# untitled.net
KiCad netlist of a schematic drawn in EAGLE
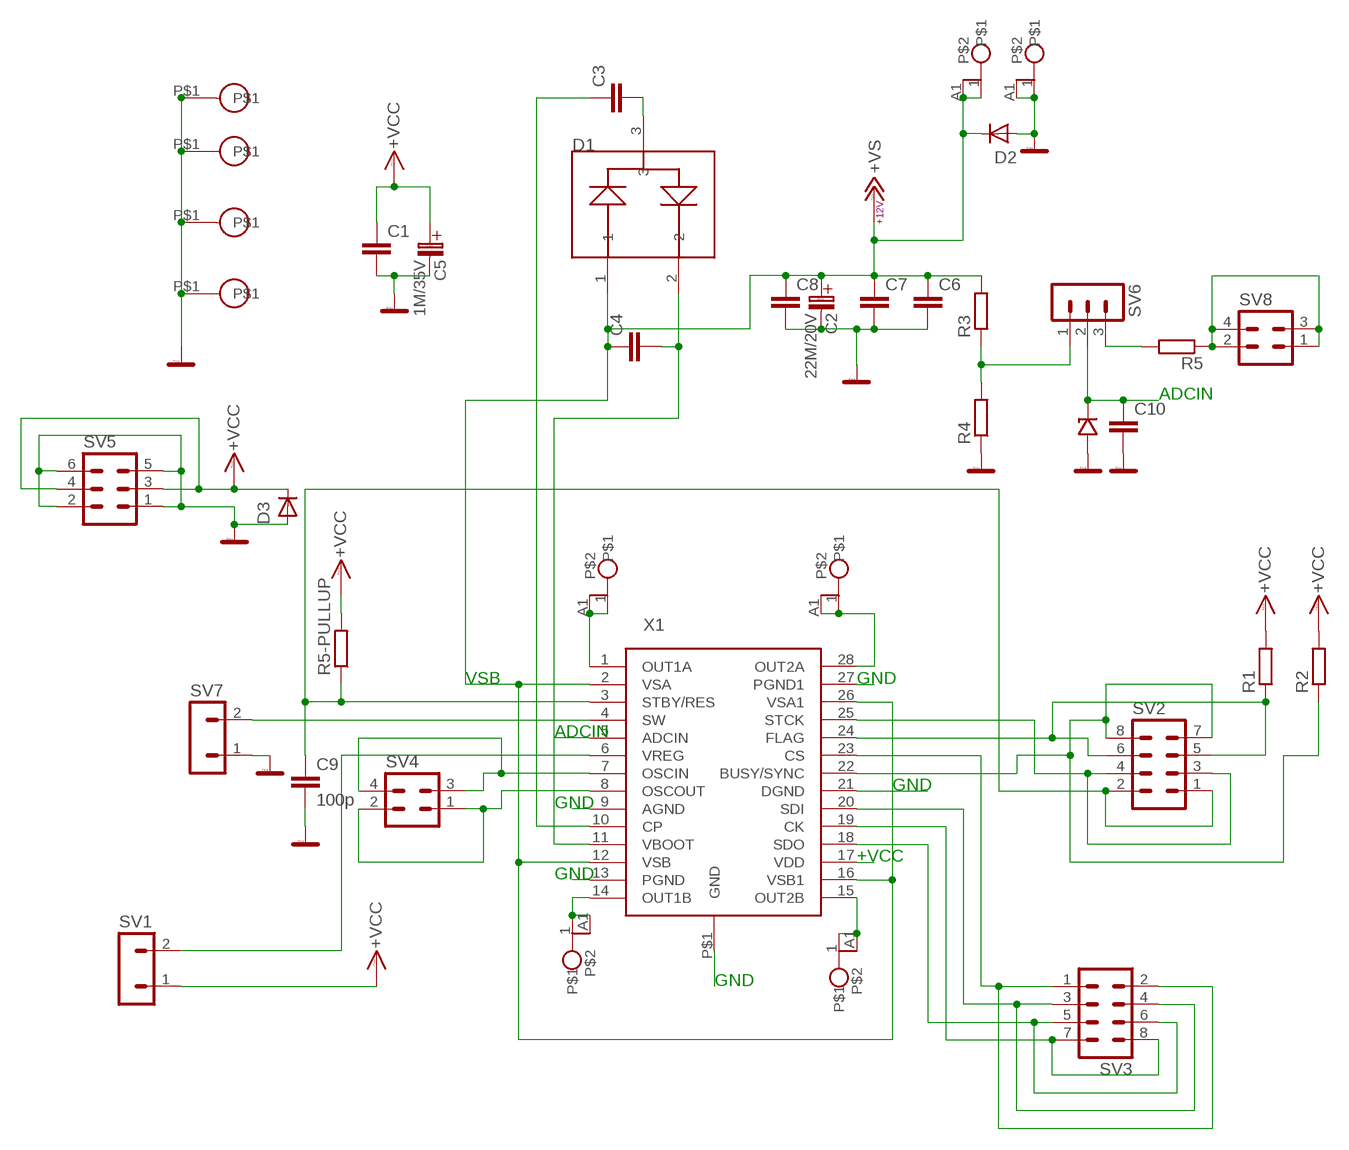
[diagram p0: schematic, sheet 1]

(export (version "E")
  (design (tool "Eeschema 10.0.6"))
  (components
    (comp (ref "C1")
      (value "C-EUC0805")
      (footprint "eagle-import:C0805")
      (libsource (lib "eagle-import") (part "C-EUC0805"))
    )
    (comp (ref "C2")
      (value "22M/20V")
      (footprint "eagle-import:D")
      (libsource (lib "eagle-import") (part "22M/20V"))
    )
    (comp (ref "C3")
      (value "C-EUC0805")
      (footprint "eagle-import:C0805")
      (libsource (lib "eagle-import") (part "C-EUC0805"))
    )
    (comp (ref "C4")
      (value "C-EUC0805")
      (footprint "eagle-import:C0805")
      (libsource (lib "eagle-import") (part "C-EUC0805"))
    )
    (comp (ref "C5")
      (value "1M/35V")
      (footprint "eagle-import:B")
      (libsource (lib "eagle-import") (part "1M/35V"))
    )
    (comp (ref "C6")
      (value "C-EUC0805")
      (footprint "eagle-import:C0805")
      (libsource (lib "eagle-import") (part "C-EUC0805"))
    )
    (comp (ref "C7")
      (value "C-EUC0805")
      (footprint "eagle-import:C0805")
      (libsource (lib "eagle-import") (part "C-EUC0805"))
    )
    (comp (ref "C8")
      (value "C-EUC0805")
      (footprint "eagle-import:C0805")
      (libsource (lib "eagle-import") (part "C-EUC0805"))
    )
    (comp (ref "C9")
      (value "100p")
      (footprint "eagle-import:C0805")
      (libsource (lib "eagle-import") (part "C-EUC0805"))
    )
    (comp (ref "C10")
      (value "C-EUC0805")
      (footprint "eagle-import:C0805")
      (libsource (lib "eagle-import") (part "C-EUC0805"))
    )
    (comp (ref "CON1")
      (value "WAGO256")
      (footprint "eagle-import:WAGO256")
      (libsource (lib "eagle-import") (part "WAGO256"))
    )
    (comp (ref "CON2")
      (value "WAGO256")
      (footprint "eagle-import:WAGO256")
      (libsource (lib "eagle-import") (part "WAGO256"))
    )
    (comp (ref "CON3")
      (value "WAGO256")
      (footprint "eagle-import:WAGO256")
      (libsource (lib "eagle-import") (part "WAGO256"))
    )
    (comp (ref "CON4")
      (value "WAGO256")
      (footprint "eagle-import:WAGO256")
      (libsource (lib "eagle-import") (part "WAGO256"))
    )
    (comp (ref "CON5")
      (value "WAGO256")
      (footprint "eagle-import:WAGO256")
      (libsource (lib "eagle-import") (part "WAGO256"))
    )
    (comp (ref "CON6")
      (value "WAGO256")
      (footprint "eagle-import:WAGO256")
      (libsource (lib "eagle-import") (part "WAGO256"))
    )
    (comp (ref "D1")
      (value "BAR43S")
      (footprint "eagle-import:SOT23")
      (libsource (lib "eagle-import") (part "BAR43S"))
    )
    (comp (ref "D2")
      (value "D-OB.")
      (footprint "eagle-import:SMB")
      (libsource (lib "eagle-import") (part "D-OB."))
    )
    (comp (ref "D3")
      (value "D-OB.SMA")
      (footprint "eagle-import:SMA")
      (libsource (lib "eagle-import") (part "D-OB.SMA"))
    )
    (comp (ref "D4")
      (value "D-ZENEROVA")
      (footprint "eagle-import:MINIMELF")
      (libsource (lib "eagle-import") (part "D-ZENEROVA"))
    )
    (comp (ref "R1")
      (value "R-EU_R0805")
      (footprint "eagle-import:R0805")
      (libsource (lib "eagle-import") (part "R-EU_R0805"))
    )
    (comp (ref "R2")
      (value "R-EU_R0805")
      (footprint "eagle-import:R0805")
      (libsource (lib "eagle-import") (part "R-EU_R0805"))
    )
    (comp (ref "R3")
      (value "R-EU_R0805")
      (footprint "eagle-import:R0805")
      (libsource (lib "eagle-import") (part "R-EU_R0805"))
    )
    (comp (ref "R4")
      (value "R-EU_R0805")
      (footprint "eagle-import:R0805")
      (libsource (lib "eagle-import") (part "R-EU_R0805"))
    )
    (comp (ref "R5")
      (value "R-EU_R0805")
      (footprint "eagle-import:R0805")
      (libsource (lib "eagle-import") (part "R-EU_R0805"))
    )
    (comp (ref "R5-PULLUP")
      (value "R-EU_R0805")
      (footprint "eagle-import:R0805")
      (libsource (lib "eagle-import") (part "R-EU_R0805"))
    )
    (comp (ref "SV1")
      (value "MA02-1")
      (footprint "eagle-import:MA02-1")
      (libsource (lib "eagle-import") (part "MA02-1"))
    )
    (comp (ref "SV2")
      (value "MA04-2")
      (footprint "eagle-import:MA04-2")
      (libsource (lib "eagle-import") (part "MA04-2"))
    )
    (comp (ref "SV3")
      (value "MA04-2")
      (footprint "eagle-import:MA04-2")
      (libsource (lib "eagle-import") (part "MA04-2"))
    )
    (comp (ref "SV4")
      (value "MA02-2")
      (footprint "eagle-import:MA02-2")
      (libsource (lib "eagle-import") (part "MA02-2"))
    )
    (comp (ref "SV5")
      (value "MA03-2")
      (footprint "eagle-import:MA03-2")
      (libsource (lib "eagle-import") (part "MA03-2"))
    )
    (comp (ref "SV6")
      (value "MA03-1")
      (footprint "eagle-import:MA03-1")
      (libsource (lib "eagle-import") (part "MA03-1"))
    )
    (comp (ref "SV7")
      (value "MA02-1")
      (footprint "eagle-import:MA02-1")
      (libsource (lib "eagle-import") (part "MA02-1"))
    )
    (comp (ref "SV8")
      (value "MA02-2")
      (footprint "eagle-import:MA02-2")
      (libsource (lib "eagle-import") (part "MA02-2"))
    )
    (comp (ref "X1")
      (value "L6470")
      (footprint "eagle-import:HTSSOP28")
      (libsource (lib "eagle-import") (part "L6470"))
    )
    (comp (ref "X3")
      (value "SROUB3M")
      (footprint "eagle-import:SROUB3M")
      (libsource (lib "eagle-import") (part "SROUB3M"))
    )
    (comp (ref "X4")
      (value "SROUB3M")
      (footprint "eagle-import:SROUB3M")
      (libsource (lib "eagle-import") (part "SROUB3M"))
    )
    (comp (ref "X5")
      (value "SROUB3M")
      (footprint "eagle-import:SROUB3M")
      (libsource (lib "eagle-import") (part "SROUB3M"))
    )
    (comp (ref "X6")
      (value "SROUB3M")
      (footprint "eagle-import:SROUB3M")
      (libsource (lib "eagle-import") (part "SROUB3M"))
    )
  )
  (nets
    (net (code "1") (name "+VCC") (class "Default")
      (node (ref "C1") (pin "1") (pinfunction "1_1") (pintype "passive"))
      (node (ref "C5") (pin "+") (pinfunction "C_EL+_+") (pintype "passive"))
      (node (ref "D3") (pin "K") (pinfunction "C_K") (pintype "passive"))
      (node (ref "R1") (pin "2") (pinfunction "2_2") (pintype "passive"))
      (node (ref "R2") (pin "2") (pinfunction "2_2") (pintype "passive"))
      (node (ref "R5-PULLUP") (pin "2") (pinfunction "2_2") (pintype "passive"))
      (node (ref "SV1") (pin "1") (pinfunction "1_1") (pintype "passive"))
      (node (ref "SV5") (pin "3") (pinfunction "3_3") (pintype "passive"))
      (node (ref "SV5") (pin "4") (pinfunction "4_4") (pintype "passive"))
      (node (ref "X1") (pin "17") (pinfunction "VDD_17") (pintype "bidirectional"))
    )
    (net (code "2") (name "+VS") (class "Default")
      (node (ref "C2") (pin "+") (pinfunction "C_EL+_+") (pintype "passive"))
      (node (ref "C4") (pin "1") (pinfunction "1_1") (pintype "passive"))
      (node (ref "C6") (pin "1") (pinfunction "1_1") (pintype "passive"))
      (node (ref "C7") (pin "1") (pinfunction "1_1") (pintype "passive"))
      (node (ref "C8") (pin "1") (pinfunction "1_1") (pintype "passive"))
      (node (ref "CON6") (pin "1") (pinfunction "P$1_1") (pintype "passive"))
      (node (ref "CON6") (pin "A1") (pinfunction "P$2_A1") (pintype "passive"))
      (node (ref "D1") (pin "1") (pinfunction "1_1") (pintype "bidirectional"))
      (node (ref "D2") (pin "K") (pinfunction "C_K") (pintype "passive"))
      (node (ref "R3") (pin "2") (pinfunction "2_2") (pintype "passive"))
      (node (ref "X1") (pin "12") (pinfunction "VSB_12") (pintype "bidirectional"))
      (node (ref "X1") (pin "16") (pinfunction "VSB1_16") (pintype "bidirectional"))
      (node (ref "X1") (pin "2") (pinfunction "VSA_2") (pintype "bidirectional"))
      (node (ref "X1") (pin "26") (pinfunction "VSA1_26") (pintype "bidirectional"))
    )
    (net (code "3") (name "/ADCIN") (class "Default")
      (node (ref "C10") (pin "1") (pinfunction "1_1") (pintype "passive"))
      (node (ref "D4") (pin "C") (pinfunction "K_C") (pintype "passive"))
      (node (ref "SV6") (pin "2") (pinfunction "2_2") (pintype "passive"))
      (node (ref "X1") (pin "5") (pinfunction "ADCIN_5") (pintype "bidirectional"))
    )
    (net (code "4") (name "GND") (class "Default")
      (node (ref "C1") (pin "2") (pinfunction "2_2") (pintype "passive"))
      (node (ref "C10") (pin "2") (pinfunction "2_2") (pintype "passive"))
      (node (ref "C2") (pin "-") (pinfunction "C_EL-_-") (pintype "passive"))
      (node (ref "C5") (pin "-") (pinfunction "C_EL-_-") (pintype "passive"))
      (node (ref "C6") (pin "2") (pinfunction "2_2") (pintype "passive"))
      (node (ref "C7") (pin "2") (pinfunction "2_2") (pintype "passive"))
      (node (ref "C8") (pin "2") (pinfunction "2_2") (pintype "passive"))
      (node (ref "C9") (pin "2") (pinfunction "2_2") (pintype "passive"))
      (node (ref "CON5") (pin "1") (pinfunction "P$1_1") (pintype "passive"))
      (node (ref "CON5") (pin "A1") (pinfunction "P$2_A1") (pintype "passive"))
      (node (ref "D2") (pin "A") (pinfunction "A_A") (pintype "passive"))
      (node (ref "D3") (pin "A") (pinfunction "A_A") (pintype "passive"))
      (node (ref "D4") (pin "A") (pinfunction "A_A") (pintype "passive"))
      (node (ref "R4") (pin "1") (pinfunction "1_1") (pintype "passive"))
      (node (ref "SV5") (pin "1") (pinfunction "1_1") (pintype "passive"))
      (node (ref "SV5") (pin "2") (pinfunction "2_2") (pintype "passive"))
      (node (ref "SV5") (pin "5") (pinfunction "5_5") (pintype "passive"))
      (node (ref "SV5") (pin "6") (pinfunction "6_6") (pintype "passive"))
      (node (ref "SV7") (pin "1") (pinfunction "1_1") (pintype "passive"))
      (node (ref "X1") (pin "13") (pinfunction "PGND_13") (pintype "bidirectional"))
      (node (ref "X1") (pin "21") (pinfunction "DGND_21") (pintype "bidirectional"))
      (node (ref "X1") (pin "27") (pinfunction "PGND1_27") (pintype "bidirectional"))
      (node (ref "X1") (pin "9") (pinfunction "AGND_9") (pintype "bidirectional"))
      (node (ref "X1") (pin "P$1") (pinfunction "GND_P$1") (pintype "bidirectional"))
      (node (ref "X3") (pin "P$1") (pinfunction "P$1_P$1") (pintype "output"))
      (node (ref "X4") (pin "P$1") (pinfunction "P$1_P$1") (pintype "output"))
      (node (ref "X5") (pin "P$1") (pinfunction "P$1_P$1") (pintype "output"))
      (node (ref "X6") (pin "P$1") (pinfunction "P$1_P$1") (pintype "output"))
    )
    (net (code "5") (name "Net-(C3-Pad2)") (class "Default")
      (node (ref "C3") (pin "2") (pinfunction "2_2") (pintype "passive"))
      (node (ref "D1") (pin "3") (pinfunction "3_3") (pintype "bidirectional"))
    )
    (net (code "6") (name "Net-(CON1-P$1)") (class "Default")
      (node (ref "CON1") (pin "1") (pinfunction "P$1_1") (pintype "passive"))
      (node (ref "CON1") (pin "A1") (pinfunction "P$2_A1") (pintype "passive"))
      (node (ref "X1") (pin "14") (pinfunction "OUT1B_14") (pintype "bidirectional"))
    )
    (net (code "7") (name "Net-(CON2-P$1)") (class "Default")
      (node (ref "CON2") (pin "1") (pinfunction "P$1_1") (pintype "passive"))
      (node (ref "CON2") (pin "A1") (pinfunction "P$2_A1") (pintype "passive"))
      (node (ref "X1") (pin "15") (pinfunction "OUT2B_15") (pintype "bidirectional"))
    )
    (net (code "8") (name "Net-(CON3-P$1)") (class "Default")
      (node (ref "CON3") (pin "1") (pinfunction "P$1_1") (pintype "passive"))
      (node (ref "CON3") (pin "A1") (pinfunction "P$2_A1") (pintype "passive"))
      (node (ref "X1") (pin "1") (pinfunction "OUT1A_1") (pintype "bidirectional"))
    )
    (net (code "9") (name "Net-(CON4-P$1)") (class "Default")
      (node (ref "CON4") (pin "1") (pinfunction "P$1_1") (pintype "passive"))
      (node (ref "CON4") (pin "A1") (pinfunction "P$2_A1") (pintype "passive"))
      (node (ref "X1") (pin "28") (pinfunction "OUT2A_28") (pintype "bidirectional"))
    )
    (net (code "10") (name "Net-(R3-Pad1)") (class "Default")
      (node (ref "R3") (pin "1") (pinfunction "1_1") (pintype "passive"))
      (node (ref "R4") (pin "2") (pinfunction "2_2") (pintype "passive"))
      (node (ref "SV6") (pin "1") (pinfunction "1_1") (pintype "passive"))
    )
    (net (code "11") (name "Net-(R5-Pad1)") (class "Default")
      (node (ref "R5") (pin "1") (pinfunction "1_1") (pintype "passive"))
      (node (ref "SV8") (pin "1") (pinfunction "1_1") (pintype "passive"))
      (node (ref "SV8") (pin "2") (pinfunction "2_2") (pintype "passive"))
      (node (ref "SV8") (pin "3") (pinfunction "3_3") (pintype "passive"))
      (node (ref "SV8") (pin "4") (pinfunction "4_4") (pintype "passive"))
    )
    (net (code "12") (name "Net-(R5-Pad2)") (class "Default")
      (node (ref "R5") (pin "2") (pinfunction "2_2") (pintype "passive"))
      (node (ref "SV6") (pin "3") (pinfunction "3_3") (pintype "passive"))
    )
    (net (code "13") (name "Net-(SV1-3)") (class "Default")
      (node (ref "SV1") (pin "2") (pinfunction "3_2") (pintype "passive"))
      (node (ref "X1") (pin "6") (pinfunction "VREG_6") (pintype "bidirectional"))
    )
    (net (code "14") (name "Net-(SV7-3)") (class "Default")
      (node (ref "SV7") (pin "2") (pinfunction "3_2") (pintype "passive"))
      (node (ref "X1") (pin "4") (pinfunction "SW_4") (pintype "bidirectional"))
    )
    (net (code "15") (name "Net-(X1-BUSY{slash}SYNC)") (class "Default")
      (node (ref "R2") (pin "1") (pinfunction "1_1") (pintype "passive"))
      (node (ref "SV2") (pin "7") (pinfunction "7_7") (pintype "passive"))
      (node (ref "SV2") (pin "8") (pinfunction "8_8") (pintype "passive"))
      (node (ref "X1") (pin "22") (pinfunction "BUSY/SYNC_22") (pintype "bidirectional"))
    )
    (net (code "16") (name "Net-(X1-CK)") (class "Default")
      (node (ref "SV3") (pin "7") (pinfunction "7_7") (pintype "passive"))
      (node (ref "SV3") (pin "8") (pinfunction "8_8") (pintype "passive"))
      (node (ref "X1") (pin "19") (pinfunction "CK_19") (pintype "bidirectional"))
    )
    (net (code "17") (name "Net-(X1-CP)") (class "Default")
      (node (ref "C3") (pin "1") (pinfunction "1_1") (pintype "passive"))
      (node (ref "X1") (pin "10") (pinfunction "CP_10") (pintype "bidirectional"))
    )
    (net (code "18") (name "Net-(X1-CS)") (class "Default")
      (node (ref "SV3") (pin "1") (pinfunction "1_1") (pintype "passive"))
      (node (ref "SV3") (pin "2") (pinfunction "2_2") (pintype "passive"))
      (node (ref "X1") (pin "23") (pinfunction "CS_23") (pintype "bidirectional"))
    )
    (net (code "19") (name "Net-(X1-FLAG)") (class "Default")
      (node (ref "R1") (pin "1") (pinfunction "1_1") (pintype "passive"))
      (node (ref "SV2") (pin "5") (pinfunction "5_5") (pintype "passive"))
      (node (ref "SV2") (pin "6") (pinfunction "6_6") (pintype "passive"))
      (node (ref "X1") (pin "24") (pinfunction "FLAG_24") (pintype "bidirectional"))
    )
    (net (code "20") (name "Net-(X1-OSCIN)") (class "Default")
      (node (ref "SV4") (pin "3") (pinfunction "3_3") (pintype "passive"))
      (node (ref "SV4") (pin "4") (pinfunction "4_4") (pintype "passive"))
      (node (ref "X1") (pin "7") (pinfunction "OSCIN_7") (pintype "bidirectional"))
    )
    (net (code "21") (name "Net-(X1-OSCOUT)") (class "Default")
      (node (ref "SV4") (pin "1") (pinfunction "1_1") (pintype "passive"))
      (node (ref "SV4") (pin "2") (pinfunction "2_2") (pintype "passive"))
      (node (ref "X1") (pin "8") (pinfunction "OSCOUT_8") (pintype "bidirectional"))
    )
    (net (code "22") (name "Net-(X1-SDI)") (class "Default")
      (node (ref "SV3") (pin "3") (pinfunction "3_3") (pintype "passive"))
      (node (ref "SV3") (pin "4") (pinfunction "4_4") (pintype "passive"))
      (node (ref "X1") (pin "20") (pinfunction "SDI_20") (pintype "bidirectional"))
    )
    (net (code "23") (name "Net-(X1-SDO)") (class "Default")
      (node (ref "SV3") (pin "5") (pinfunction "5_5") (pintype "passive"))
      (node (ref "SV3") (pin "6") (pinfunction "6_6") (pintype "passive"))
      (node (ref "X1") (pin "18") (pinfunction "SDO_18") (pintype "bidirectional"))
    )
    (net (code "24") (name "Net-(X1-STBY{slash}RES)") (class "Default")
      (node (ref "C9") (pin "1") (pinfunction "1_1") (pintype "passive"))
      (node (ref "R5-PULLUP") (pin "1") (pinfunction "1_1") (pintype "passive"))
      (node (ref "SV2") (pin "1") (pinfunction "1_1") (pintype "passive"))
      (node (ref "SV2") (pin "2") (pinfunction "2_2") (pintype "passive"))
      (node (ref "X1") (pin "3") (pinfunction "STBY/RES_3") (pintype "bidirectional"))
    )
    (net (code "25") (name "Net-(X1-STCK)") (class "Default")
      (node (ref "SV2") (pin "3") (pinfunction "3_3") (pintype "passive"))
      (node (ref "SV2") (pin "4") (pinfunction "4_4") (pintype "passive"))
      (node (ref "X1") (pin "25") (pinfunction "STCK_25") (pintype "bidirectional"))
    )
    (net (code "26") (name "Net-(X1-VBOOT)") (class "Default")
      (node (ref "C4") (pin "2") (pinfunction "2_2") (pintype "passive"))
      (node (ref "D1") (pin "2") (pinfunction "2_2") (pintype "bidirectional"))
      (node (ref "X1") (pin "11") (pinfunction "VBOOT_11") (pintype "bidirectional"))
    )
  )
)
